# led.net
KiCad netlist of a schematic drawn in EAGLE
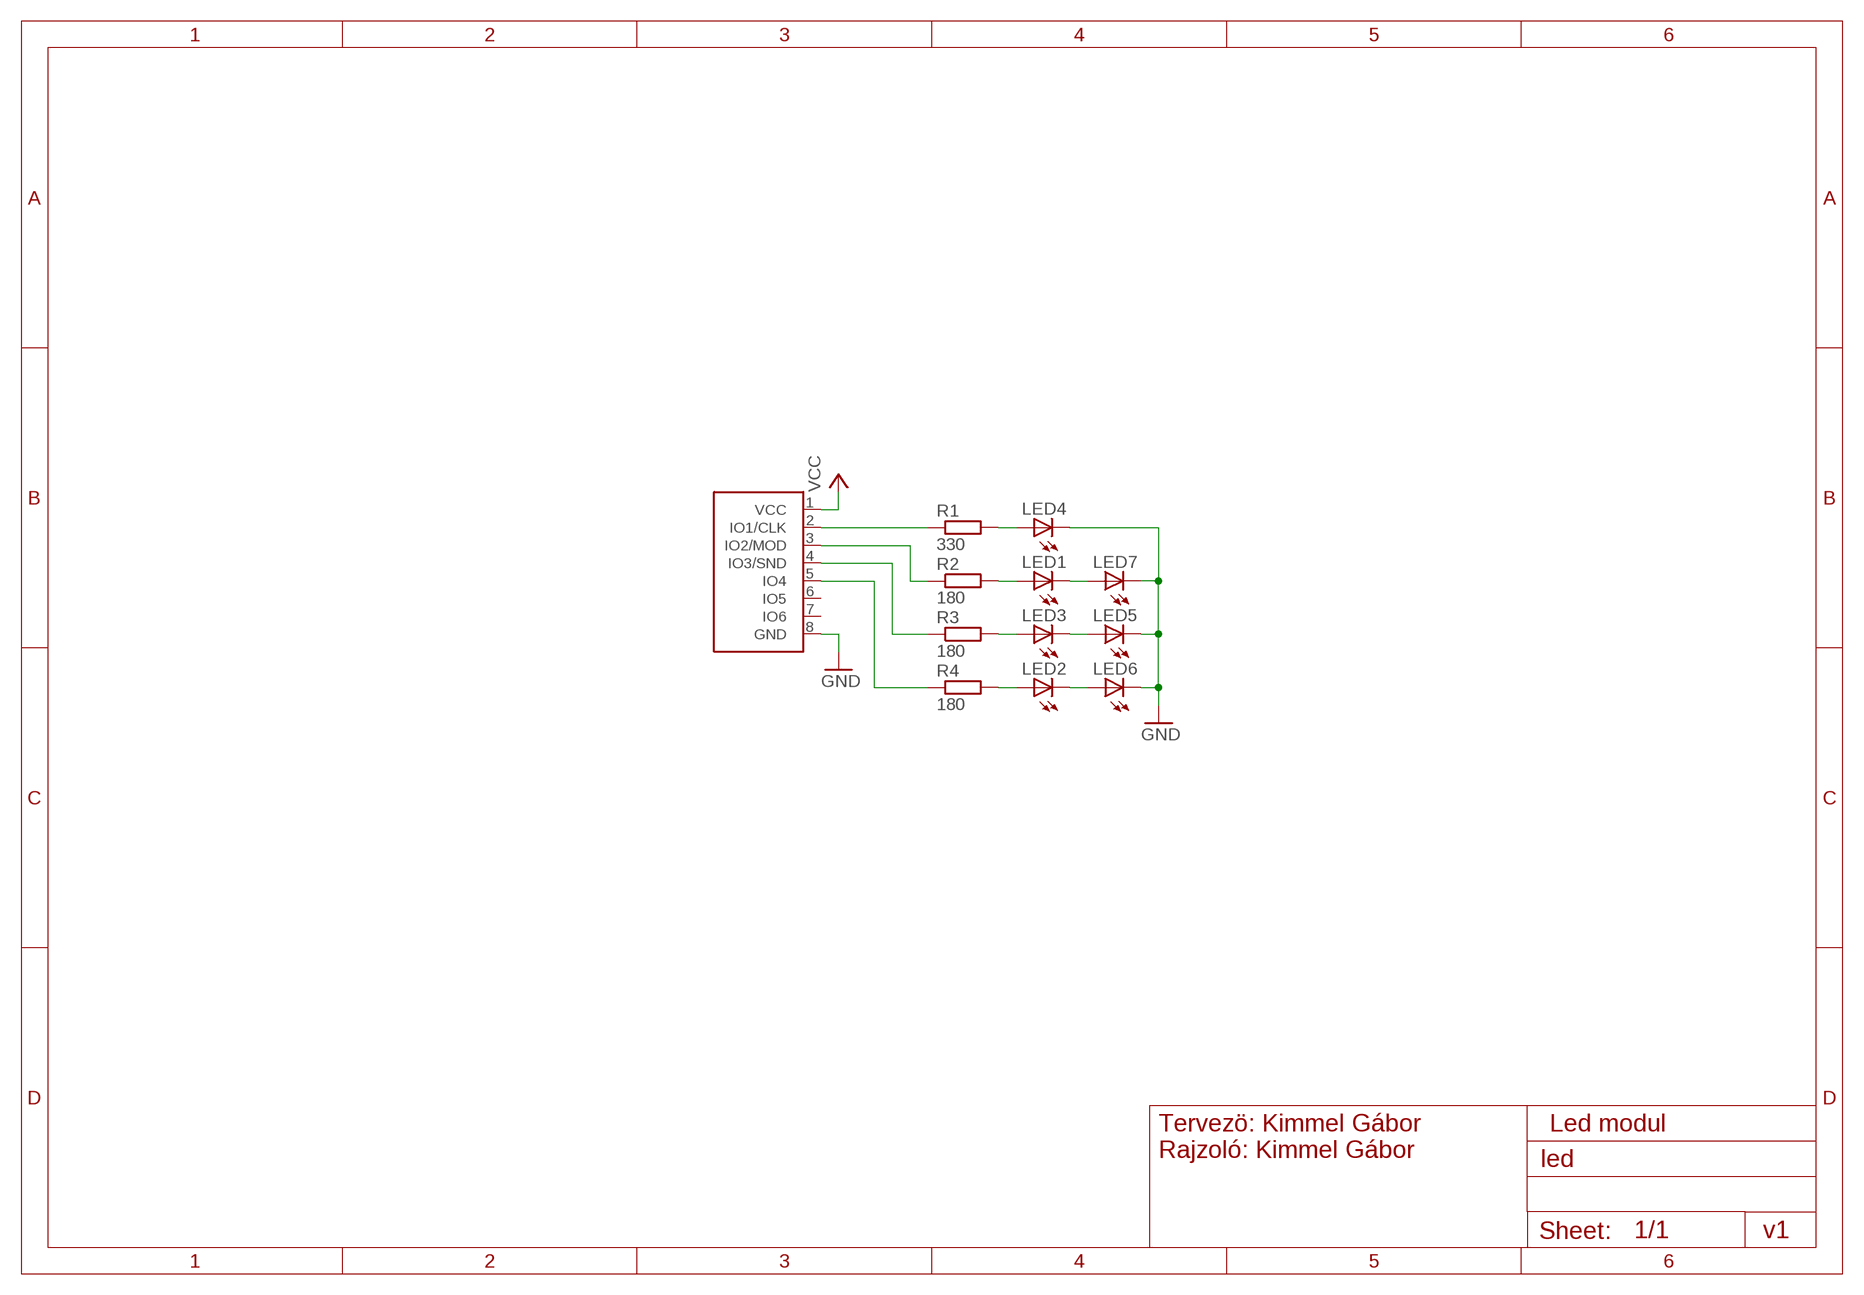
[diagram p0: schematic, sheet 1]

(export (version "E")
  (design (tool "Eeschema 10.0.6"))
  (components
    (comp (ref "LED1")
      (value "LED5MM")
      (footprint "eagle-import:LED5MM")
      (libsource (lib "eagle-import") (part "LED5MM"))
    )
    (comp (ref "LED2")
      (value "LED5MM")
      (footprint "eagle-import:LED5MM")
      (libsource (lib "eagle-import") (part "LED5MM"))
    )
    (comp (ref "LED3")
      (value "LED5MM")
      (footprint "eagle-import:LED5MM")
      (libsource (lib "eagle-import") (part "LED5MM"))
    )
    (comp (ref "LED4")
      (value "LED5MM")
      (footprint "eagle-import:LED5MM")
      (libsource (lib "eagle-import") (part "LED5MM"))
    )
    (comp (ref "LED5")
      (value "LED5MM")
      (footprint "eagle-import:LED5MM")
      (libsource (lib "eagle-import") (part "LED5MM"))
    )
    (comp (ref "LED6")
      (value "LED5MM")
      (footprint "eagle-import:LED5MM")
      (libsource (lib "eagle-import") (part "LED5MM"))
    )
    (comp (ref "LED7")
      (value "LED5MM")
      (footprint "eagle-import:LED5MM")
      (libsource (lib "eagle-import") (part "LED5MM"))
    )
    (comp (ref "R1")
      (value "330")
      (footprint "eagle-import:0207_10")
      (libsource (lib "eagle-import") (part "R-EU_0207/10"))
    )
    (comp (ref "R2")
      (value "180")
      (footprint "eagle-import:0207_10")
      (libsource (lib "eagle-import") (part "R-EU_0207/10"))
    )
    (comp (ref "R3")
      (value "180")
      (footprint "eagle-import:0207_10")
      (libsource (lib "eagle-import") (part "R-EU_0207/10"))
    )
    (comp (ref "R4")
      (value "180")
      (footprint "eagle-import:0207_10")
      (libsource (lib "eagle-import") (part "R-EU_0207/10"))
    )
    (comp (ref "U$1")
      (value "GANZ-CONNECTOR")
      (footprint "eagle-import:FE08W")
      (libsource (lib "eagle-import") (part "GANZ-CONNECTOR"))
    )
  )
  (nets
    (net (code "1") (name "GND") (class "Default")
      (node (ref "LED4") (pin "K") (pinfunction "C_K") (pintype "passive"))
      (node (ref "LED5") (pin "K") (pinfunction "C_K") (pintype "passive"))
      (node (ref "LED6") (pin "K") (pinfunction "C_K") (pintype "passive"))
      (node (ref "LED7") (pin "K") (pinfunction "C_K") (pintype "passive"))
      (node (ref "U$1") (pin "8") (pinfunction "GND_8") (pintype "bidirectional"))
    )
    (net (code "2") (name "Net-(LED1-C)") (class "Default")
      (node (ref "LED1") (pin "K") (pinfunction "C_K") (pintype "passive"))
      (node (ref "LED7") (pin "A") (pinfunction "A_A") (pintype "passive"))
    )
    (net (code "3") (name "Net-(LED1-PadA)") (class "Default")
      (node (ref "LED1") (pin "A") (pinfunction "A_A") (pintype "passive"))
      (node (ref "R2") (pin "2") (pinfunction "2_2") (pintype "passive"))
    )
    (net (code "4") (name "Net-(LED2-C)") (class "Default")
      (node (ref "LED2") (pin "K") (pinfunction "C_K") (pintype "passive"))
      (node (ref "LED6") (pin "A") (pinfunction "A_A") (pintype "passive"))
    )
    (net (code "5") (name "Net-(LED2-PadA)") (class "Default")
      (node (ref "LED2") (pin "A") (pinfunction "A_A") (pintype "passive"))
      (node (ref "R4") (pin "2") (pinfunction "2_2") (pintype "passive"))
    )
    (net (code "6") (name "Net-(LED3-C)") (class "Default")
      (node (ref "LED3") (pin "K") (pinfunction "C_K") (pintype "passive"))
      (node (ref "LED5") (pin "A") (pinfunction "A_A") (pintype "passive"))
    )
    (net (code "7") (name "Net-(LED3-PadA)") (class "Default")
      (node (ref "LED3") (pin "A") (pinfunction "A_A") (pintype "passive"))
      (node (ref "R3") (pin "2") (pinfunction "2_2") (pintype "passive"))
    )
    (net (code "8") (name "Net-(LED4-PadA)") (class "Default")
      (node (ref "LED4") (pin "A") (pinfunction "A_A") (pintype "passive"))
      (node (ref "R1") (pin "2") (pinfunction "2_2") (pintype "passive"))
    )
    (net (code "9") (name "Net-(U$1-IO1{slash}CLK)") (class "Default")
      (node (ref "R1") (pin "1") (pinfunction "1_1") (pintype "passive"))
      (node (ref "U$1") (pin "2") (pinfunction "IO1/CLK_2") (pintype "bidirectional"))
    )
    (net (code "10") (name "Net-(U$1-IO2{slash}MOD)") (class "Default")
      (node (ref "R2") (pin "1") (pinfunction "1_1") (pintype "passive"))
      (node (ref "U$1") (pin "3") (pinfunction "IO2/MOD_3") (pintype "bidirectional"))
    )
    (net (code "11") (name "Net-(U$1-IO3{slash}SND)") (class "Default")
      (node (ref "R3") (pin "1") (pinfunction "1_1") (pintype "passive"))
      (node (ref "U$1") (pin "4") (pinfunction "IO3/SND_4") (pintype "bidirectional"))
    )
    (net (code "12") (name "Net-(U$1-IO4)") (class "Default")
      (node (ref "R4") (pin "1") (pinfunction "1_1") (pintype "passive"))
      (node (ref "U$1") (pin "5") (pinfunction "IO4_5") (pintype "bidirectional"))
    )
    (net (code "13") (name "VCC") (class "Default")
      (node (ref "U$1") (pin "1") (pinfunction "VCC_1") (pintype "bidirectional"))
    )
    (net (code "14") (name "unconnected-(U$1-IO5-Pad6)") (class "Default")
      (node (ref "U$1") (pin "6") (pinfunction "IO5_6") (pintype "bidirectional"))
    )
    (net (code "15") (name "unconnected-(U$1-IO6-Pad7)") (class "Default")
      (node (ref "U$1") (pin "7") (pinfunction "IO6_7") (pintype "bidirectional"))
    )
  )
)
